# POWER_UNIT.net
KiCad netlist of a schematic drawn in Altium Designer
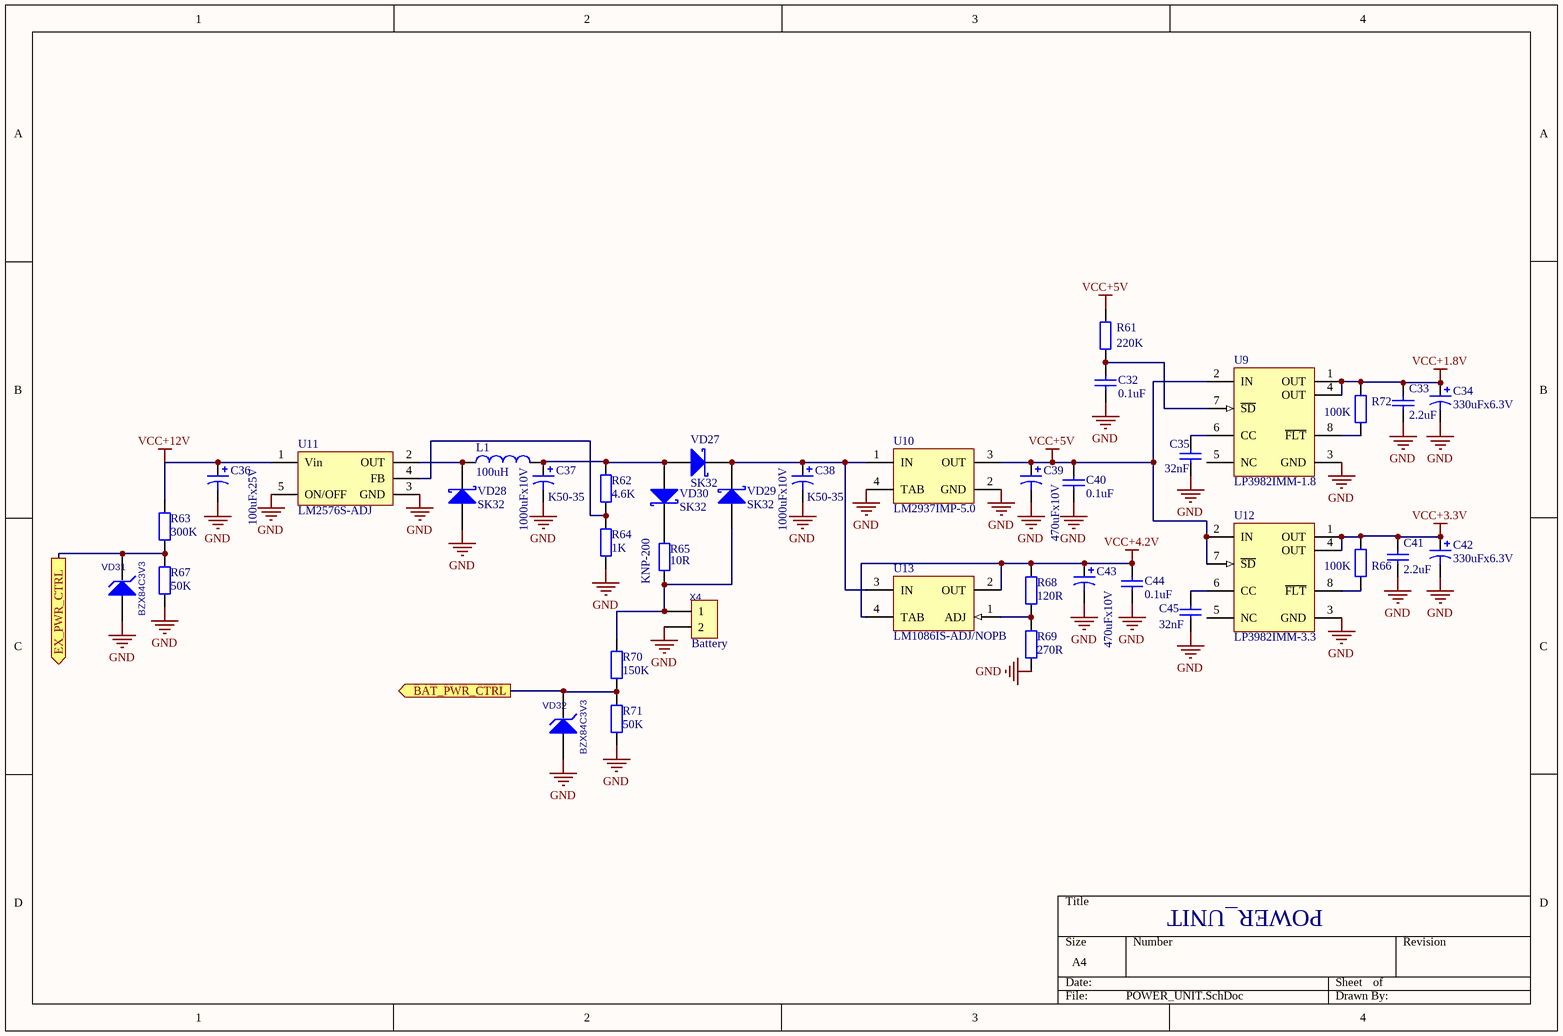
[diagram p0: POWER_UNIT.SchDoc]

(export (version "E")
  (design (tool "Eeschema 10.0.6"))
  (components
    (comp (ref "C32")
      (value "0.1uF")
      (footprint "C0603")
      (description "Capasitor_SMD_0808/")
      (fields (field (name "Comment") "0805"))
      (libsource (lib "NEW") (part "Capasitor_SMD_0805"))
    )
    (comp (ref "C33")
      (value "2.2uF")
      (footprint "C0603")
      (description "Capasitor_SMD_0808/")
      (fields (field (name "Comment") "0805"))
      (libsource (lib "NEW") (part "Capasitor_SMD_0805"))
    )
    (comp (ref "C34")
      (value "330uFx6.3V")
      (footprint "Capasitor_POL_SMD D6.3")
      (fields (field (name "Comment") "SMD_cap"))
      (libsource (lib "NEW") (part "Capasitor_POL_SMD D8.0"))
    )
    (comp (ref "C35")
      (value "32nF")
      (footprint "C0603")
      (description "Capasitor_SMD_0808/")
      (fields (field (name "Comment") "0805"))
      (libsource (lib "NEW") (part "Capasitor_SMD_0805"))
    )
    (comp (ref "C36")
      (value "100uFx25V")
      (footprint "CAP_POL_D6.3")
      (fields (field (name "Comment") "K50-35"))
      (libsource (lib "NEW") (part "Capasitor_pol D6.3"))
    )
    (comp (ref "C37")
      (value "K50-35")
      (footprint "CAP_POL_D10")
      (fields (field (name "ALTIUM_VALUE") "1000uFx10V"))
      (libsource (lib "NEW") (part "Capasitor_pol D10"))
    )
    (comp (ref "C38")
      (value "K50-35")
      (footprint "CAP_POL_D10")
      (fields (field (name "ALTIUM_VALUE") "1000uFx10V"))
      (libsource (lib "NEW") (part "Capasitor_pol D10"))
    )
    (comp (ref "C39")
      (value "470uFx10V")
      (footprint "Capasitor_POL_SMD D8")
      (description "size 8x10.5")
      (fields (field (name "Comment") "SMD_cap"))
      (libsource (lib "NEW") (part "Capasitor_POL_SMD D8.0"))
    )
    (comp (ref "C40")
      (value "0.1uF")
      (footprint "C0603")
      (description "Capasitor_SMD_0808/")
      (fields (field (name "Comment") "0805"))
      (libsource (lib "NEW") (part "Capasitor_SMD_0805"))
    )
    (comp (ref "C41")
      (value "2.2uF")
      (footprint "C0603")
      (description "Capasitor_SMD_0808/")
      (fields (field (name "Comment") "0805"))
      (libsource (lib "NEW") (part "Capasitor_SMD_0805"))
    )
    (comp (ref "C42")
      (value "330uFx6.3V")
      (footprint "Capasitor_POL_SMD D6.3")
      (fields (field (name "Comment") "SMD_cap"))
      (libsource (lib "NEW") (part "Capasitor_POL_SMD D8.0"))
    )
    (comp (ref "C43")
      (value "470uFx10V")
      (footprint "Capasitor_POL_SMD D8")
      (description "size 8x10.5")
      (fields (field (name "Comment") "SMD_cap"))
      (libsource (lib "NEW") (part "Capasitor_POL_SMD D8.0"))
    )
    (comp (ref "C44")
      (value "0.1uF")
      (footprint "C0603")
      (description "Capasitor_SMD_0808/")
      (fields (field (name "Comment") "0805"))
      (libsource (lib "NEW") (part "Capasitor_SMD_0805"))
    )
    (comp (ref "C45")
      (value "32nF")
      (footprint "C0603")
      (description "Capasitor_SMD_0808/")
      (fields (field (name "Comment") "0805"))
      (libsource (lib "NEW") (part "Capasitor_SMD_0805"))
    )
    (comp (ref "L1")
      (value "100uH")
      (footprint "Inductor_SMD_12.5x12.5")
      (fields (field (name "Comment") "B82477P4"))
      (libsource (lib "NEW") (part "B82477P4"))
    )
    (comp (ref "R61")
      (value "220K")
      (footprint "C0603")
      (description "Resistor")
      (fields (field (name "Comment") "RES"))
      (libsource (lib "NEW") (part "RES"))
    )
    (comp (ref "R62")
      (value "4.6K")
      (footprint "C0603")
      (description "Resistor")
      (fields (field (name "Comment") "RES"))
      (libsource (lib "NEW") (part "RES"))
    )
    (comp (ref "R63")
      (value "300K")
      (footprint "C0603")
      (description "Resistor")
      (fields (field (name "Comment") "RES"))
      (libsource (lib "NEW") (part "RES"))
    )
    (comp (ref "R64")
      (value "1K")
      (footprint "C0603")
      (description "Resistor")
      (fields (field (name "Comment") "RES"))
      (libsource (lib "NEW") (part "RES"))
    )
    (comp (ref "R65")
      (value "KNP-200")
      (footprint "Resistor KNP-200")
      (fields (field (name "ALTIUM_VALUE") "10R"))
      (libsource (lib "NEW") (part "Resistor 2W"))
    )
    (comp (ref "R66")
      (value "100K")
      (footprint "C0603")
      (description "Resistor")
      (fields (field (name "Comment") "RES"))
      (libsource (lib "NEW") (part "RES"))
    )
    (comp (ref "R67")
      (value "50K")
      (footprint "C0603")
      (description "Resistor")
      (fields (field (name "Comment") "RES"))
      (libsource (lib "NEW") (part "RES"))
    )
    (comp (ref "R68")
      (value "120R")
      (footprint "C0805")
      (description "Resistor")
      (fields (field (name "Comment") "RES"))
      (libsource (lib "NEW") (part "RES"))
    )
    (comp (ref "R69")
      (value "270R")
      (footprint "C0805")
      (description "Resistor")
      (fields (field (name "Comment") "RES"))
      (libsource (lib "NEW") (part "RES"))
    )
    (comp (ref "R70")
      (value "150K")
      (footprint "C0603")
      (description "Resistor")
      (fields (field (name "Comment") "RES"))
      (libsource (lib "NEW") (part "RES"))
    )
    (comp (ref "R71")
      (value "50K")
      (footprint "C0603")
      (description "Resistor")
      (fields (field (name "Comment") "RES"))
      (libsource (lib "NEW") (part "RES"))
    )
    (comp (ref "R72")
      (value "100K")
      (footprint "C0603")
      (description "Resistor")
      (fields (field (name "Comment") "RES"))
      (libsource (lib "NEW") (part "RES"))
    )
    (comp (ref "U9")
      (value "LP3982IMM-1.8")
      (footprint "MUA08A_N")
      (description "Micropower, Ultra Low-Dropout, Low-Noise, 300mA CMOS Regulator, 8-pin Mini SOIC")
      (fields
        (field (name "MANUFACTURER") "National Semiconductor")
        (field (name "PUBLISHER") "Altium Limited")
      )
      (libsource (lib "NSC LDO") (part "LP3982IMM-1.8"))
    )
    (comp (ref "U10")
      (value "LM2937IMP-5.0")
      (footprint "MP04A_N")
      (description "500 mA Low Dropout Regulator, 4-pin SOT-223")
      (fields
        (field (name "MANUFACTURER") "National Semiconductor")
        (field (name "PUBLISHER") "Altium Limited")
      )
      (libsource (lib "NSC LDO") (part "LM2937IMP-5.0"))
    )
    (comp (ref "U11")
      (value "LM2576S-ADJ")
      (footprint "TO-263-5")
      (libsource (lib "NEW") (part "LM2576S-ADJ"))
    )
    (comp (ref "U12")
      (value "LP3982IMM-3.3")
      (footprint "MUA08A_N")
      (description "Micropower, Ultra Low-Dropout, Low-Noise, 300mA CMOS Regulator, 8-pin Mini SOIC")
      (fields
        (field (name "MANUFACTURER") "National Semiconductor")
        (field (name "PUBLISHER") "Altium Limited")
      )
      (libsource (lib "NSC LDO") (part "LP3982IMM-3.3"))
    )
    (comp (ref "U13")
      (value "LM1086IS-ADJ/NOPB")
      (footprint "TS3B_N")
      (description "1.5A Low Dropout Positive Regulators, 3-pin TO-263, Pb-Free")
      (fields
        (field (name "MANUFACTURER") "National Semiconductor")
        (field (name "PUBLISHER") "Altium Limited")
      )
      (libsource (lib "NSC LDO") (part "LM1086IS-ADJ/NOPB"))
    )
    (comp (ref "VD27") (value "SK32") (footprint "SMC") (libsource (lib "NEW") (part "SK32")))
    (comp (ref "VD28") (value "SK32") (footprint "SMC") (libsource (lib "NEW") (part "SK32")))
    (comp (ref "VD29") (value "SK32") (footprint "SMC") (libsource (lib "NEW") (part "SK32")))
    (comp (ref "VD30") (value "SK32") (footprint "SMC") (libsource (lib "NEW") (part "SK32")))
    (comp (ref "VD31")
      (value "BZX84C3V3")
      (footprint "SOT23")
      (description "BZX84C")
      (libsource (lib "NEW") (part "BZX84C"))
    )
    (comp (ref "VD32")
      (value "BZX84C3V3")
      (footprint "SOT23")
      (description "BZX84C")
      (libsource (lib "NEW") (part "BZX84C"))
    )
    (comp (ref "X4")
      (value "Battery")
      (footprint "DG350-3.5-2P")
      (description "DG350-3.5-2P")
      (libsource (lib "NEW") (part "DG350-3.5-2P"))
    )
  )
  (nets
    (net (code "1") (name "/BAT_PWR_CTRL") (class "Default")
      (node (ref "R70") (pin "1") (pinfunction "1_1") (pintype "passive"))
      (node (ref "R71") (pin "2") (pinfunction "2_2") (pintype "passive"))
      (node (ref "VD32") (pin "3") (pinfunction "K_3") (pintype "passive"))
    )
    (net (code "2") (name "/EX_PWR_CTRL") (class "Default")
      (node (ref "R63") (pin "1") (pinfunction "1_1") (pintype "passive"))
      (node (ref "R67") (pin "2") (pinfunction "2_2") (pintype "passive"))
      (node (ref "VD31") (pin "3") (pinfunction "K_3") (pintype "passive"))
    )
    (net (code "3") (name "GND") (class "Default")
      (node (ref "C32") (pin "2") (pinfunction "2_2") (pintype "passive"))
      (node (ref "C33") (pin "2") (pinfunction "2_2") (pintype "passive"))
      (node (ref "C34") (pin "2") (pinfunction "2_2") (pintype "passive"))
      (node (ref "C35") (pin "2") (pinfunction "2_2") (pintype "passive"))
      (node (ref "C36") (pin "2") (pinfunction "2_2") (pintype "passive"))
      (node (ref "C37") (pin "2") (pinfunction "2_2") (pintype "passive"))
      (node (ref "C38") (pin "2") (pinfunction "2_2") (pintype "passive"))
      (node (ref "C39") (pin "2") (pinfunction "2_2") (pintype "passive"))
      (node (ref "C40") (pin "2") (pinfunction "2_2") (pintype "passive"))
      (node (ref "C41") (pin "2") (pinfunction "2_2") (pintype "passive"))
      (node (ref "C42") (pin "2") (pinfunction "2_2") (pintype "passive"))
      (node (ref "C43") (pin "2") (pinfunction "2_2") (pintype "passive"))
      (node (ref "C44") (pin "2") (pinfunction "2_2") (pintype "passive"))
      (node (ref "C45") (pin "2") (pinfunction "2_2") (pintype "passive"))
      (node (ref "R64") (pin "1") (pinfunction "1_1") (pintype "passive"))
      (node (ref "R67") (pin "1") (pinfunction "1_1") (pintype "passive"))
      (node (ref "R69") (pin "1") (pinfunction "1_1") (pintype "passive"))
      (node (ref "R71") (pin "1") (pinfunction "1_1") (pintype "passive"))
      (node (ref "U10") (pin "2") (pinfunction "GND_2") (pintype "power_in"))
      (node (ref "U10") (pin "4") (pinfunction "TAB_4") (pintype "power_in"))
      (node (ref "U11") (pin "3") (pinfunction "GND_3") (pintype "passive"))
      (node (ref "U11") (pin "5") (pinfunction "ON/OFF_5") (pintype "passive"))
      (node (ref "U12") (pin "3") (pinfunction "GND_3") (pintype "power_in"))
      (node (ref "U9") (pin "3") (pinfunction "GND_3") (pintype "power_in"))
      (node (ref "VD28") (pin "2") (pinfunction "A_2") (pintype "passive"))
      (node (ref "VD31") (pin "1") (pinfunction "A_1") (pintype "passive"))
      (node (ref "VD32") (pin "1") (pinfunction "A_1") (pintype "passive"))
      (node (ref "X4") (pin "2") (pinfunction "2_2") (pintype "passive"))
    )
    (net (code "4") (name "Net-(U9-CC)") (class "Default")
      (node (ref "C35") (pin "1") (pinfunction "1_1") (pintype "passive"))
      (node (ref "U9") (pin "6") (pinfunction "CC_6") (pintype "passive"))
    )
    (net (code "5") (name "Net-(U9-~{FLT})") (class "Default")
      (node (ref "R72") (pin "1") (pinfunction "1_1") (pintype "passive"))
      (node (ref "U9") (pin "8") (pinfunction "~{FLT}_8") (pintype "open_collector"))
    )
    (net (code "6") (name "Net-(U9-~{SD})") (class "Default")
      (node (ref "C32") (pin "1") (pinfunction "1_1") (pintype "passive"))
      (node (ref "R61") (pin "1") (pinfunction "1_1") (pintype "passive"))
      (node (ref "U9") (pin "7") (pinfunction "~{SD}_7") (pintype "input"))
    )
    (net (code "7") (name "Net-(U10-IN)") (class "Default")
      (node (ref "C38") (pin "1") (pinfunction "1_1") (pintype "passive"))
      (node (ref "U10") (pin "1") (pinfunction "IN_1") (pintype "power_in"))
      (node (ref "U13") (pin "3") (pinfunction "IN_3") (pintype "power_in"))
      (node (ref "VD27") (pin "1") (pinfunction "K_1") (pintype "passive"))
      (node (ref "VD29") (pin "1") (pinfunction "K_1") (pintype "passive"))
    )
    (net (code "8") (name "Net-(U11-FB)") (class "Default")
      (node (ref "R62") (pin "1") (pinfunction "1_1") (pintype "passive"))
      (node (ref "R64") (pin "2") (pinfunction "2_2") (pintype "passive"))
      (node (ref "U11") (pin "4") (pinfunction "FB_4") (pintype "passive"))
    )
    (net (code "9") (name "Net-(U11-OUT)") (class "Default")
      (node (ref "L1") (pin "1") (pinfunction "1_1") (pintype "passive"))
      (node (ref "U11") (pin "2") (pinfunction "OUT_2") (pintype "passive"))
      (node (ref "VD28") (pin "1") (pinfunction "K_1") (pintype "passive"))
    )
    (net (code "10") (name "Net-(U12-CC)") (class "Default")
      (node (ref "C45") (pin "1") (pinfunction "1_1") (pintype "passive"))
      (node (ref "U12") (pin "6") (pinfunction "CC_6") (pintype "passive"))
    )
    (net (code "11") (name "Net-(U12-~{FLT})") (class "Default")
      (node (ref "R66") (pin "1") (pinfunction "1_1") (pintype "passive"))
      (node (ref "U12") (pin "8") (pinfunction "~{FLT}_8") (pintype "open_collector"))
    )
    (net (code "12") (name "Net-(U13-ADJ)") (class "Default")
      (node (ref "R68") (pin "1") (pinfunction "1_1") (pintype "passive"))
      (node (ref "R69") (pin "2") (pinfunction "2_2") (pintype "passive"))
      (node (ref "U13") (pin "1") (pinfunction "ADJ_1") (pintype "input"))
    )
    (net (code "13") (name "Net-(VD27-A)") (class "Default")
      (node (ref "C37") (pin "1") (pinfunction "1_1") (pintype "passive"))
      (node (ref "L1") (pin "2") (pinfunction "2_2") (pintype "passive"))
      (node (ref "R62") (pin "2") (pinfunction "2_2") (pintype "passive"))
      (node (ref "VD27") (pin "2") (pinfunction "A_2") (pintype "passive"))
      (node (ref "VD30") (pin "2") (pinfunction "A_2") (pintype "passive"))
    )
    (net (code "14") (name "Net-(VD29-A)") (class "Default")
      (node (ref "R65") (pin "1") (pinfunction "1_1") (pintype "passive"))
      (node (ref "R70") (pin "2") (pinfunction "2_2") (pintype "passive"))
      (node (ref "VD29") (pin "2") (pinfunction "A_2") (pintype "passive"))
      (node (ref "X4") (pin "1") (pinfunction "1_1") (pintype "passive"))
    )
    (net (code "15") (name "Net-(VD30-K)") (class "Default")
      (node (ref "R65") (pin "2") (pinfunction "2_2") (pintype "passive"))
      (node (ref "VD30") (pin "1") (pinfunction "K_1") (pintype "passive"))
    )
    (net (code "16") (name "VCC+1.8V") (class "Default")
      (node (ref "C33") (pin "1") (pinfunction "1_1") (pintype "passive"))
      (node (ref "C34") (pin "1") (pinfunction "1_1") (pintype "passive"))
      (node (ref "R72") (pin "2") (pinfunction "2_2") (pintype "passive"))
      (node (ref "U9") (pin "1") (pinfunction "OUT_1") (pintype "power_in"))
      (node (ref "U9") (pin "4") (pinfunction "OUT_4") (pintype "power_in"))
    )
    (net (code "17") (name "VCC+3.3V") (class "Default")
      (node (ref "C41") (pin "1") (pinfunction "1_1") (pintype "passive"))
      (node (ref "C42") (pin "1") (pinfunction "1_1") (pintype "passive"))
      (node (ref "R66") (pin "2") (pinfunction "2_2") (pintype "passive"))
      (node (ref "U12") (pin "1") (pinfunction "OUT_1") (pintype "power_in"))
      (node (ref "U12") (pin "4") (pinfunction "OUT_4") (pintype "power_in"))
    )
    (net (code "18") (name "VCC+4.2V") (class "Default")
      (node (ref "C43") (pin "1") (pinfunction "1_1") (pintype "passive"))
      (node (ref "C44") (pin "1") (pinfunction "1_1") (pintype "passive"))
      (node (ref "R68") (pin "2") (pinfunction "2_2") (pintype "passive"))
      (node (ref "U13") (pin "2") (pinfunction "OUT_2") (pintype "power_in"))
      (node (ref "U13") (pin "4") (pinfunction "TAB_4") (pintype "power_in"))
    )
    (net (code "19") (name "VCC+5V") (class "Default")
      (node (ref "C39") (pin "1") (pinfunction "1_1") (pintype "passive"))
      (node (ref "C40") (pin "1") (pinfunction "1_1") (pintype "passive"))
      (node (ref "R61") (pin "2") (pinfunction "2_2") (pintype "passive"))
      (node (ref "U10") (pin "3") (pinfunction "OUT_3") (pintype "power_in"))
      (node (ref "U12") (pin "2") (pinfunction "IN_2") (pintype "power_in"))
      (node (ref "U12") (pin "7") (pinfunction "~{SD}_7") (pintype "input"))
      (node (ref "U9") (pin "2") (pinfunction "IN_2") (pintype "power_in"))
    )
    (net (code "20") (name "VCC+12V") (class "Default")
      (node (ref "C36") (pin "1") (pinfunction "1_1") (pintype "passive"))
      (node (ref "R63") (pin "2") (pinfunction "2_2") (pintype "passive"))
      (node (ref "U11") (pin "1") (pinfunction "Vin_1") (pintype "passive"))
    )
    (net (code "21") (name "unconnected-(U9-NC-Pad5)") (class "Default")
      (node (ref "U9") (pin "5") (pinfunction "NC_5") (pintype "passive"))
    )
    (net (code "22") (name "unconnected-(U12-NC-Pad5)") (class "Default")
      (node (ref "U12") (pin "5") (pinfunction "NC_5") (pintype "passive"))
    )
    (net (code "23") (name "unconnected-(VD31-Pad2)") (class "Default")
      (node (ref "VD31") (pin "2") (pintype "passive"))
    )
    (net (code "24") (name "unconnected-(VD32-Pad2)") (class "Default")
      (node (ref "VD32") (pin "2") (pintype "passive"))
    )
  )
)
